# ext_supply.net
KiCad netlist of a schematic drawn in Altium Designer
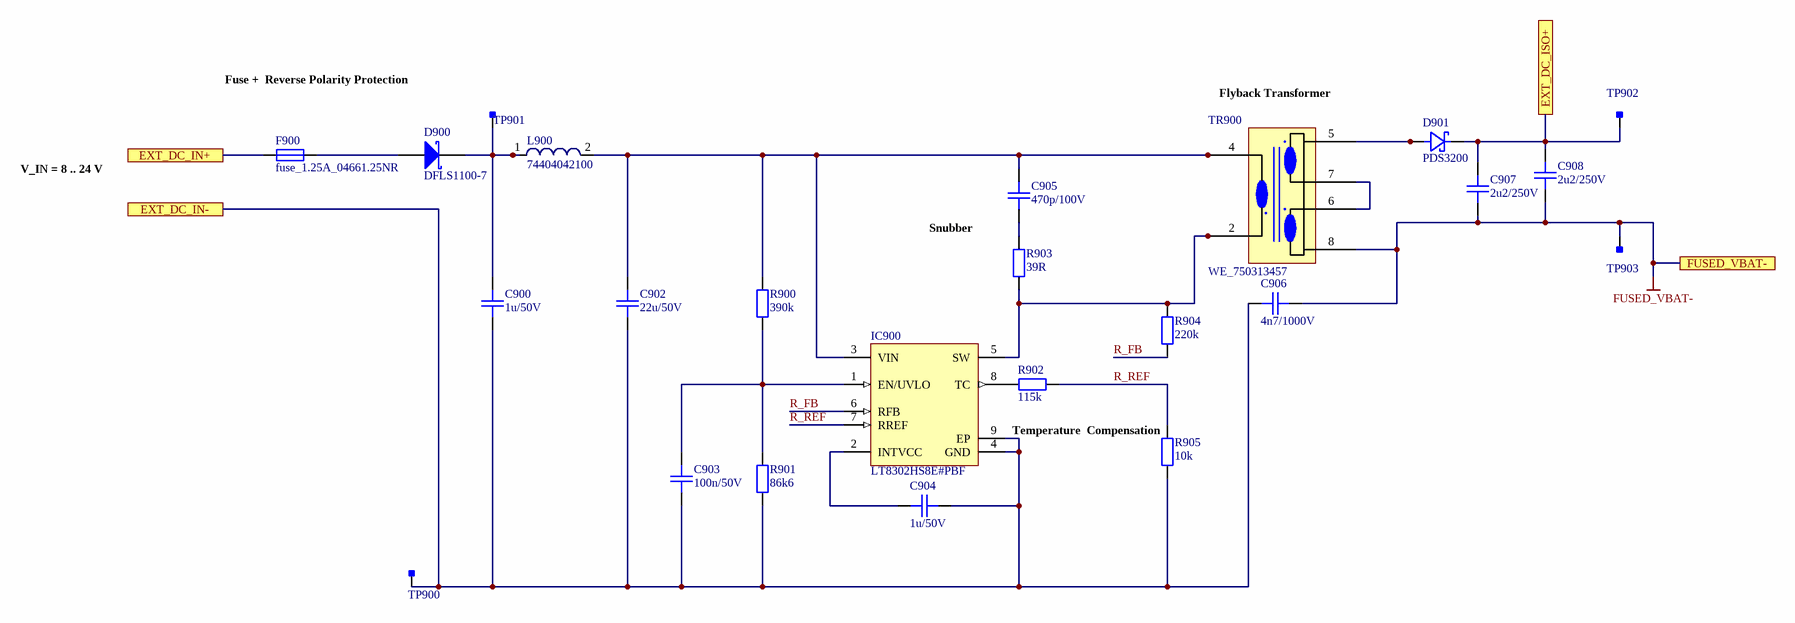
[diagram p0: ext_supply.SchDoc]

(export (version "E")
  (design (tool "Eeschema 10.0.6"))
  (components
    (comp (ref "C900")
      (value "1u/50V")
      (footprint "CAPC2012X14N")
      (description "MLCC")
      (fields (field (name "PART NUMBER") "gen_C_ceramic_1u_50V_X7R_0805") (field (name "TOLERANCE") "± 10%"))
      (libsource (lib "OE750") (part "C"))
    )
    (comp (ref "C902")
      (value "22u/50V")
      (footprint "CAPC2220(5750)230_N")
      (description "MLCC")
      (fields (field (name "PART NUMBER") "gen_C_ceramic_22u_50V_X7R_2220_stacked"))
      (libsource (lib "OE750") (part "C"))
    )
    (comp (ref "C903")
      (value "100n/50V")
      (footprint "CAPC1608X08N")
      (description "MLCC")
      (fields (field (name "PART NUMBER") "gen_C_ceramic_100n_50V_X7R_0603"))
      (libsource (lib "OE750") (part "C"))
    )
    (comp (ref "C904")
      (value "1u/50V")
      (footprint "CAPC2012X14N")
      (description "MLCC")
      (fields (field (name "PART NUMBER") "gen_C_ceramic_1u_50V_X7R_0805") (field (name "TOLERANCE") "± 10%"))
      (libsource (lib "OE750") (part "C"))
    )
    (comp (ref "C905")
      (value "470p/100V")
      (footprint "CAPC2012X14N")
      (description "MLCC")
      (fields (field (name "PART NUMBER") "gen_C_ceramic_470p_100V_X7R_0805"))
      (libsource (lib "OE750") (part "C"))
    )
    (comp (ref "C906")
      (value "4n7/1000V")
      (footprint "CAPC4532X16N")
      (description "MLCC")
      (fields (field (name "PART NUMBER") "gen_C_ceramic_4n7_1000V_X7R_1812"))
      (libsource (lib "OE750") (part "C"))
    )
    (comp (ref "C907")
      (value "2u2/250V")
      (footprint "CAPC2220(5750)230_N")
      (description "MLCC")
      (fields (field (name "PART NUMBER") "gen_C_ceramic_2u2_250V_X7R_2220"))
      (libsource (lib "OE750") (part "C"))
    )
    (comp (ref "C908")
      (value "2u2/250V")
      (footprint "CAPC2220(5750)230_N")
      (description "MLCC")
      (fields (field (name "PART NUMBER") "gen_C_ceramic_2u2_250V_X7R_2220"))
      (libsource (lib "OE750") (part "C"))
    )
    (comp (ref "D900")
      (value "DFLS1100-7")
      (footprint "DIOD-POWERDI123-2_V")
      (fields (field (name "MANUFACTURER") "Diodes Inc"))
      (libsource (lib "Altium Content Vault") (part "DSKY-AK-2"))
    )
    (comp (ref "D901")
      (value "PDS3200")
      (footprint "PowerDI5")
      (description "Schottky Diode 3A 200V 780mV")
      (fields (field (name "PART NUMBER") "PDS3200-13") (field (name "MANUFACTURER") "DIODES Inc"))
      (libsource (lib "OE750") (part "PDS3200"))
    )
    (comp (ref "F900")
      (value "fuse_1.25A_04661.25NR")
      (footprint "LITTLEFUSE_466")
      (description "Fuse, Surface Mount, 466 Series, 1.25 A, 63 VAC, 63 VDC, Very Fast Acting, 1206")
      (fields (field (name "MANUFACTURER") "Littlefuse"))
      (libsource (lib "OE750") (part "R_Fuse"))
    )
    (comp (ref "IC900")
      (value "LT8302HS8E#PBF")
      (footprint "LT-S8E-8_V")
      (fields (field (name "PARTNUMBER") "LT8302"))
      (libsource (lib "Altium Content Vault") (part "LT-LT8302-S8E-8"))
    )
    (comp (ref "L900")
      (value "74404042100")
      (footprint "WE-LQS 4018")
      (description "WE-LQS SMD Power Inductor, L=10 µH")
      (fields (field (name "MANUFACTURER") "Wuerth Elektronik"))
      (libsource (lib "Altium Content Vault") (part "WE-IND-INDUCTOR-2"))
    )
    (comp (ref "R900")
      (value "390k")
      (footprint "RESC1608X05N")
      (description "SMD Resistor 390k 0603")
      (fields (field (name "PART NUMBER") "gen_R_390k_0603") (field (name "TOLERANCE") "1%"))
      (libsource (lib "OE750") (part "R"))
    )
    (comp (ref "R901")
      (value "86k6")
      (footprint "RESC1608X05N")
      (description "SMD Resistor 86k6 0603")
      (fields (field (name "PART NUMBER") "gen_R_86k6_0603") (field (name "TOLERANCE") "1%"))
      (libsource (lib "OE750") (part "R"))
    )
    (comp (ref "R902")
      (value "115k")
      (footprint "RESC1608X05N")
      (description "SMD Resistor 115k 0603")
      (fields (field (name "PART NUMBER") "gen_R_115k_0603") (field (name "TOLERANCE") "1%"))
      (libsource (lib "OE750") (part "R"))
    )
    (comp (ref "R903")
      (value "39R")
      (footprint "RESC2012X05N")
      (description "SMD Resistor 39R 0805")
      (fields (field (name "PART NUMBER") "gen_R_39R_0805") (field (name "TOLERANCE") "1%"))
      (libsource (lib "OE750") (part "R"))
    )
    (comp (ref "R904")
      (value "220k")
      (footprint "RESC1608X05N")
      (description "SMD Resistor 220k 0603")
      (fields (field (name "PART NUMBER") "gen_R_220k_0603") (field (name "TOLERANCE") "1%"))
      (libsource (lib "OE750") (part "R"))
    )
    (comp (ref "R905")
      (value "10k")
      (footprint "RESC1608X05N")
      (description "SMD Resistor 10k 0603")
      (fields (field (name "PART NUMBER") "gen_R_10k_0603") (field (name "TOLERANCE") "1%"))
      (libsource (lib "OE750") (part "R"))
    )
    (comp (ref "TP900")
      (value "Testpoint_Square")
      (footprint "Testpoint_S1")
      (description "Testpoint, square")
      (libsource (lib "OE750") (part "Testpoint_Square"))
    )
    (comp (ref "TP901")
      (value "Testpoint_Square")
      (footprint "Testpoint_S1")
      (description "Testpoint, square")
      (libsource (lib "OE750") (part "Testpoint_Square"))
    )
    (comp (ref "TP902")
      (value "Testpoint_Square")
      (footprint "Testpoint_S1")
      (description "Testpoint, square")
      (libsource (lib "OE750") (part "Testpoint_Square"))
    )
    (comp (ref "TP903")
      (value "Testpoint_Square")
      (footprint "Testpoint_S1")
      (description "Testpoint, square")
      (libsource (lib "OE750") (part "Testpoint_Square"))
    )
    (comp (ref "TR900")
      (value "WE_750313457")
      (footprint "WE_750313457")
      (description "MID-FLYLT Flyback Transformers for Linear Technology")
      (fields (field (name "MANUFACTURER") "Würth Elektronik"))
      (libsource (lib "OE750") (part "WE_750313457"))
    )
  )
  (nets
    (net (code "1") (name "/EXT_DC_IN+") (class "Default")
      (node (ref "F900") (pin "1") (pinfunction "1_1") (pintype "passive"))
    )
    (net (code "2") (name "/EXT_DC_IN-") (class "Default")
      (node (ref "C900") (pin "1") (pinfunction "1_1") (pintype "passive"))
      (node (ref "C902") (pin "1") (pinfunction "1_1") (pintype "passive"))
      (node (ref "C903") (pin "1") (pinfunction "1_1") (pintype "passive"))
      (node (ref "C904") (pin "1") (pinfunction "1_1") (pintype "passive"))
      (node (ref "C906") (pin "1") (pinfunction "1_1") (pintype "passive"))
      (node (ref "IC900") (pin "4") (pinfunction "GND_4") (pintype "power_in"))
      (node (ref "IC900") (pin "9") (pinfunction "EP_9") (pintype "power_in"))
      (node (ref "R901") (pin "1") (pinfunction "1_1") (pintype "passive"))
      (node (ref "R905") (pin "1") (pinfunction "1_1") (pintype "passive"))
      (node (ref "TP900") (pin "1") (pinfunction "1_1") (pintype "passive"))
    )
    (net (code "3") (name "/EXT_DC_ISO+") (class "Default")
      (node (ref "C907") (pin "2") (pinfunction "2_2") (pintype "passive"))
      (node (ref "C908") (pin "2") (pinfunction "2_2") (pintype "passive"))
      (node (ref "D901") (pin "1") (pinfunction "C_1") (pintype "passive"))
      (node (ref "TP902") (pin "1") (pinfunction "1_1") (pintype "passive"))
    )
    (net (code "4") (name "/R_FB") (class "Default")
      (node (ref "IC900") (pin "6") (pinfunction "RFB_6") (pintype "input"))
      (node (ref "R904") (pin "1") (pinfunction "1_1") (pintype "passive"))
    )
    (net (code "5") (name "/R_REF") (class "Default")
      (node (ref "IC900") (pin "7") (pinfunction "RREF_7") (pintype "input"))
      (node (ref "R902") (pin "2") (pinfunction "2_2") (pintype "passive"))
      (node (ref "R905") (pin "2") (pinfunction "2_2") (pintype "passive"))
    )
    (net (code "6") (name "FUSED_VBAT-") (class "Default")
      (node (ref "C906") (pin "2") (pinfunction "2_2") (pintype "passive"))
      (node (ref "C907") (pin "1") (pinfunction "1_1") (pintype "passive"))
      (node (ref "C908") (pin "1") (pinfunction "1_1") (pintype "passive"))
      (node (ref "TP903") (pin "1") (pinfunction "1_1") (pintype "passive"))
      (node (ref "TR900") (pin "8") (pinfunction "8_8") (pintype "passive"))
    )
    (net (code "7") (name "Net-(C905-Pad1)") (class "Default")
      (node (ref "C905") (pin "1") (pinfunction "1_1") (pintype "passive"))
      (node (ref "R903") (pin "2") (pinfunction "2_2") (pintype "passive"))
    )
    (net (code "8") (name "Net-(D900-A)") (class "Default")
      (node (ref "D900") (pin "1") (pinfunction "A_1") (pintype "passive"))
      (node (ref "F900") (pin "2") (pinfunction "2_2") (pintype "passive"))
    )
    (net (code "9") (name "Net-(D900-K)") (class "Default")
      (node (ref "C900") (pin "2") (pinfunction "2_2") (pintype "passive"))
      (node (ref "D900") (pin "2") (pinfunction "K_2") (pintype "passive"))
      (node (ref "L900") (pin "1") (pinfunction "1_1") (pintype "passive"))
      (node (ref "TP901") (pin "1") (pinfunction "1_1") (pintype "passive"))
    )
    (net (code "10") (name "Net-(D901-A-Pad2)") (class "Default")
      (node (ref "D901") (pin "2") (pinfunction "A_2") (pintype "passive"))
      (node (ref "D901") (pin "3") (pinfunction "A_3") (pintype "passive"))
      (node (ref "TR900") (pin "5") (pinfunction "5_5") (pintype "passive"))
    )
    (net (code "11") (name "Net-(IC900-EN{slash}UVLO)") (class "Default")
      (node (ref "C903") (pin "2") (pinfunction "2_2") (pintype "passive"))
      (node (ref "IC900") (pin "1") (pinfunction "EN/UVLO_1") (pintype "input"))
      (node (ref "R900") (pin "1") (pinfunction "1_1") (pintype "passive"))
      (node (ref "R901") (pin "2") (pinfunction "2_2") (pintype "passive"))
    )
    (net (code "12") (name "Net-(IC900-INTVCC)") (class "Default")
      (node (ref "C904") (pin "2") (pinfunction "2_2") (pintype "passive"))
      (node (ref "IC900") (pin "2") (pinfunction "INTVCC_2") (pintype "power_in"))
    )
    (net (code "13") (name "Net-(IC900-SW)") (class "Default")
      (node (ref "IC900") (pin "5") (pinfunction "SW_5") (pintype "power_in"))
      (node (ref "R903") (pin "1") (pinfunction "1_1") (pintype "passive"))
      (node (ref "R904") (pin "2") (pinfunction "2_2") (pintype "passive"))
      (node (ref "TR900") (pin "1") (pinfunction "1_1") (pintype "passive"))
      (node (ref "TR900") (pin "2") (pinfunction "2_2") (pintype "passive"))
    )
    (net (code "14") (name "Net-(IC900-TC)") (class "Default")
      (node (ref "IC900") (pin "8") (pinfunction "TC_8") (pintype "output"))
      (node (ref "R902") (pin "1") (pinfunction "1_1") (pintype "passive"))
    )
    (net (code "15") (name "Net-(IC900-VIN)") (class "Default")
      (node (ref "C902") (pin "2") (pinfunction "2_2") (pintype "passive"))
      (node (ref "C905") (pin "2") (pinfunction "2_2") (pintype "passive"))
      (node (ref "IC900") (pin "3") (pinfunction "VIN_3") (pintype "power_in"))
      (node (ref "L900") (pin "2") (pinfunction "2_2") (pintype "passive"))
      (node (ref "R900") (pin "2") (pinfunction "2_2") (pintype "passive"))
      (node (ref "TR900") (pin "3") (pinfunction "3_3") (pintype "passive"))
      (node (ref "TR900") (pin "4") (pinfunction "4_4") (pintype "passive"))
    )
    (net (code "16") (name "Net-(TR900-Pad6)") (class "Default")
      (node (ref "TR900") (pin "6") (pinfunction "6_6") (pintype "passive"))
      (node (ref "TR900") (pin "7") (pinfunction "7_7") (pintype "passive"))
    )
  )
)
